# Ethernet_Switch.net
KiCad netlist of a schematic drawn in Altium Designer
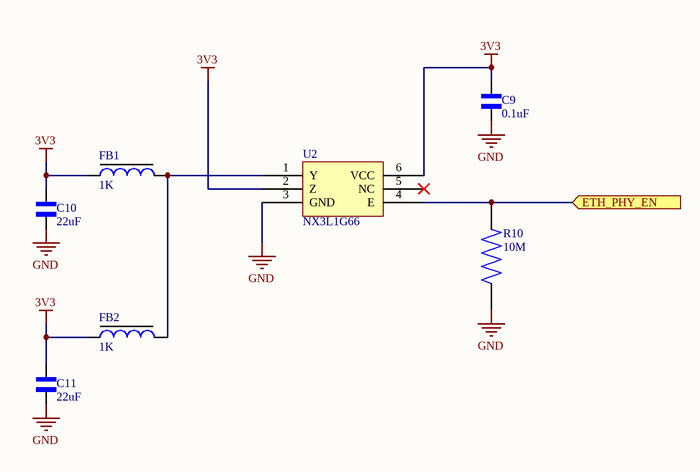
[diagram p0: Ethernet_Switch.SchDoc]

(export (version "E")
  (design (tool "Eeschema 10.0.6"))
  (components
    (comp (ref "C9")
      (value "0.1uF")
      (footprint "C0402")
      (description "CAP CER 0.1UF 6.3V X5R 01005")
      (fields
        (field (name "MANUFACTURER") "Murata")
        (field (name "MANUFACTURER PART NUMBER") "GRM022R60J104KE15L")
      )
      (libsource (lib "nnts") (part "GRM022R60J104KE15L"))
    )
    (comp (ref "C10")
      (value "22uF")
      (footprint "C0603")
      (description "0603 22 uF 10 V ±20% Tolerance X5R Surface Mount Multilayer Ceramic Capacitor")
      (fields
        (field (name "MANUFACTURER") "Murata")
        (field (name "MANUFACTURER PART NUMBER") "ZRB18AR61A226ME01L")
      )
      (libsource (lib "nnts") (part "ZRB18AR61A226ME01L"))
    )
    (comp (ref "C11")
      (value "22uF")
      (footprint "C0603")
      (description "0603 22 uF 10 V ±20% Tolerance X5R Surface Mount Multilayer Ceramic Capacitor")
      (fields
        (field (name "MANUFACTURER") "Murata")
        (field (name "MANUFACTURER PART NUMBER") "ZRB18AR61A226ME01L")
      )
      (libsource (lib "nnts") (part "ZRB18AR61A226ME01L"))
    )
    (comp (ref "FB1")
      (value "1K")
      (footprint "FB0402")
      (description "FERRITE BEAD 1 KOHM 0402 1LN")
      (fields
        (field (name "MANUFACTURER") "Murata")
        (field (name "MANUFACTURER PART NUMBER") "BLM15AG102SH1D")
      )
      (libsource (lib "nnts") (part "BLM15AG102SH1D"))
    )
    (comp (ref "FB2")
      (value "1K")
      (footprint "FB0402")
      (description "FERRITE BEAD 1 KOHM 0402 1LN")
      (fields
        (field (name "MANUFACTURER") "Murata")
        (field (name "MANUFACTURER PART NUMBER") "BLM15AG102SH1D")
      )
      (libsource (lib "nnts") (part "BLM15AG102SH1D"))
    )
    (comp (ref "R10")
      (value "10M")
      (footprint "R0402 Vishay")
      (fields
        (field (name "MANUFACTURER") "Vishay")
        (field (name "MANUFACTURER PART NUMBER") "CRCW040210M0FKED")
        (field (name "TOLERANCE") "1%")
      )
      (libsource (lib "nnts") (part "CRCW040210M0FKED"))
    )
    (comp (ref "U2")
      (value "NX3L1G66")
      (footprint "PSON50P145X100X50-6N")
      (description "Single pole Single Throw switch")
      (libsource (lib "nnts") (part "NX3L1G66"))
    )
  )
  (nets
    (net (code "1") (name "/ETH_PHY_EN") (class "Default")
      (node (ref "R10") (pin "2") (pinfunction "2_2") (pintype "passive"))
      (node (ref "U2") (pin "4") (pinfunction "E_4") (pintype "passive"))
    )
    (net (code "2") (name "3V3") (class "Default")
      (node (ref "C10") (pin "2") (pinfunction "2_2") (pintype "passive"))
      (node (ref "C11") (pin "2") (pinfunction "2_2") (pintype "passive"))
      (node (ref "C9") (pin "2") (pinfunction "2_2") (pintype "passive"))
      (node (ref "FB1") (pin "1") (pinfunction "1_1") (pintype "passive"))
      (node (ref "FB2") (pin "1") (pinfunction "1_1") (pintype "passive"))
      (node (ref "U2") (pin "2") (pinfunction "Z_2") (pintype "passive"))
      (node (ref "U2") (pin "6") (pinfunction "VCC_6") (pintype "passive"))
    )
    (net (code "3") (name "GND") (class "Default")
      (node (ref "C10") (pin "1") (pinfunction "1_1") (pintype "passive"))
      (node (ref "C11") (pin "1") (pinfunction "1_1") (pintype "passive"))
      (node (ref "C9") (pin "1") (pinfunction "1_1") (pintype "passive"))
      (node (ref "R10") (pin "1") (pinfunction "1_1") (pintype "passive"))
      (node (ref "U2") (pin "3") (pinfunction "GND_3") (pintype "passive"))
    )
    (net (code "4") (name "Net-(U2-Y)") (class "Default")
      (node (ref "FB1") (pin "2") (pinfunction "2_2") (pintype "passive"))
      (node (ref "FB2") (pin "2") (pinfunction "2_2") (pintype "passive"))
      (node (ref "U2") (pin "1") (pinfunction "Y_1") (pintype "passive"))
    )
    (net (code "5") (name "unconnected-(U2-NC-Pad5)") (class "Default")
      (node (ref "U2") (pin "5") (pinfunction "NC_5") (pintype "passive+no_connect"))
    )
  )
)
